# MAIN.net
KiCad netlist of a schematic drawn in Altium Designer
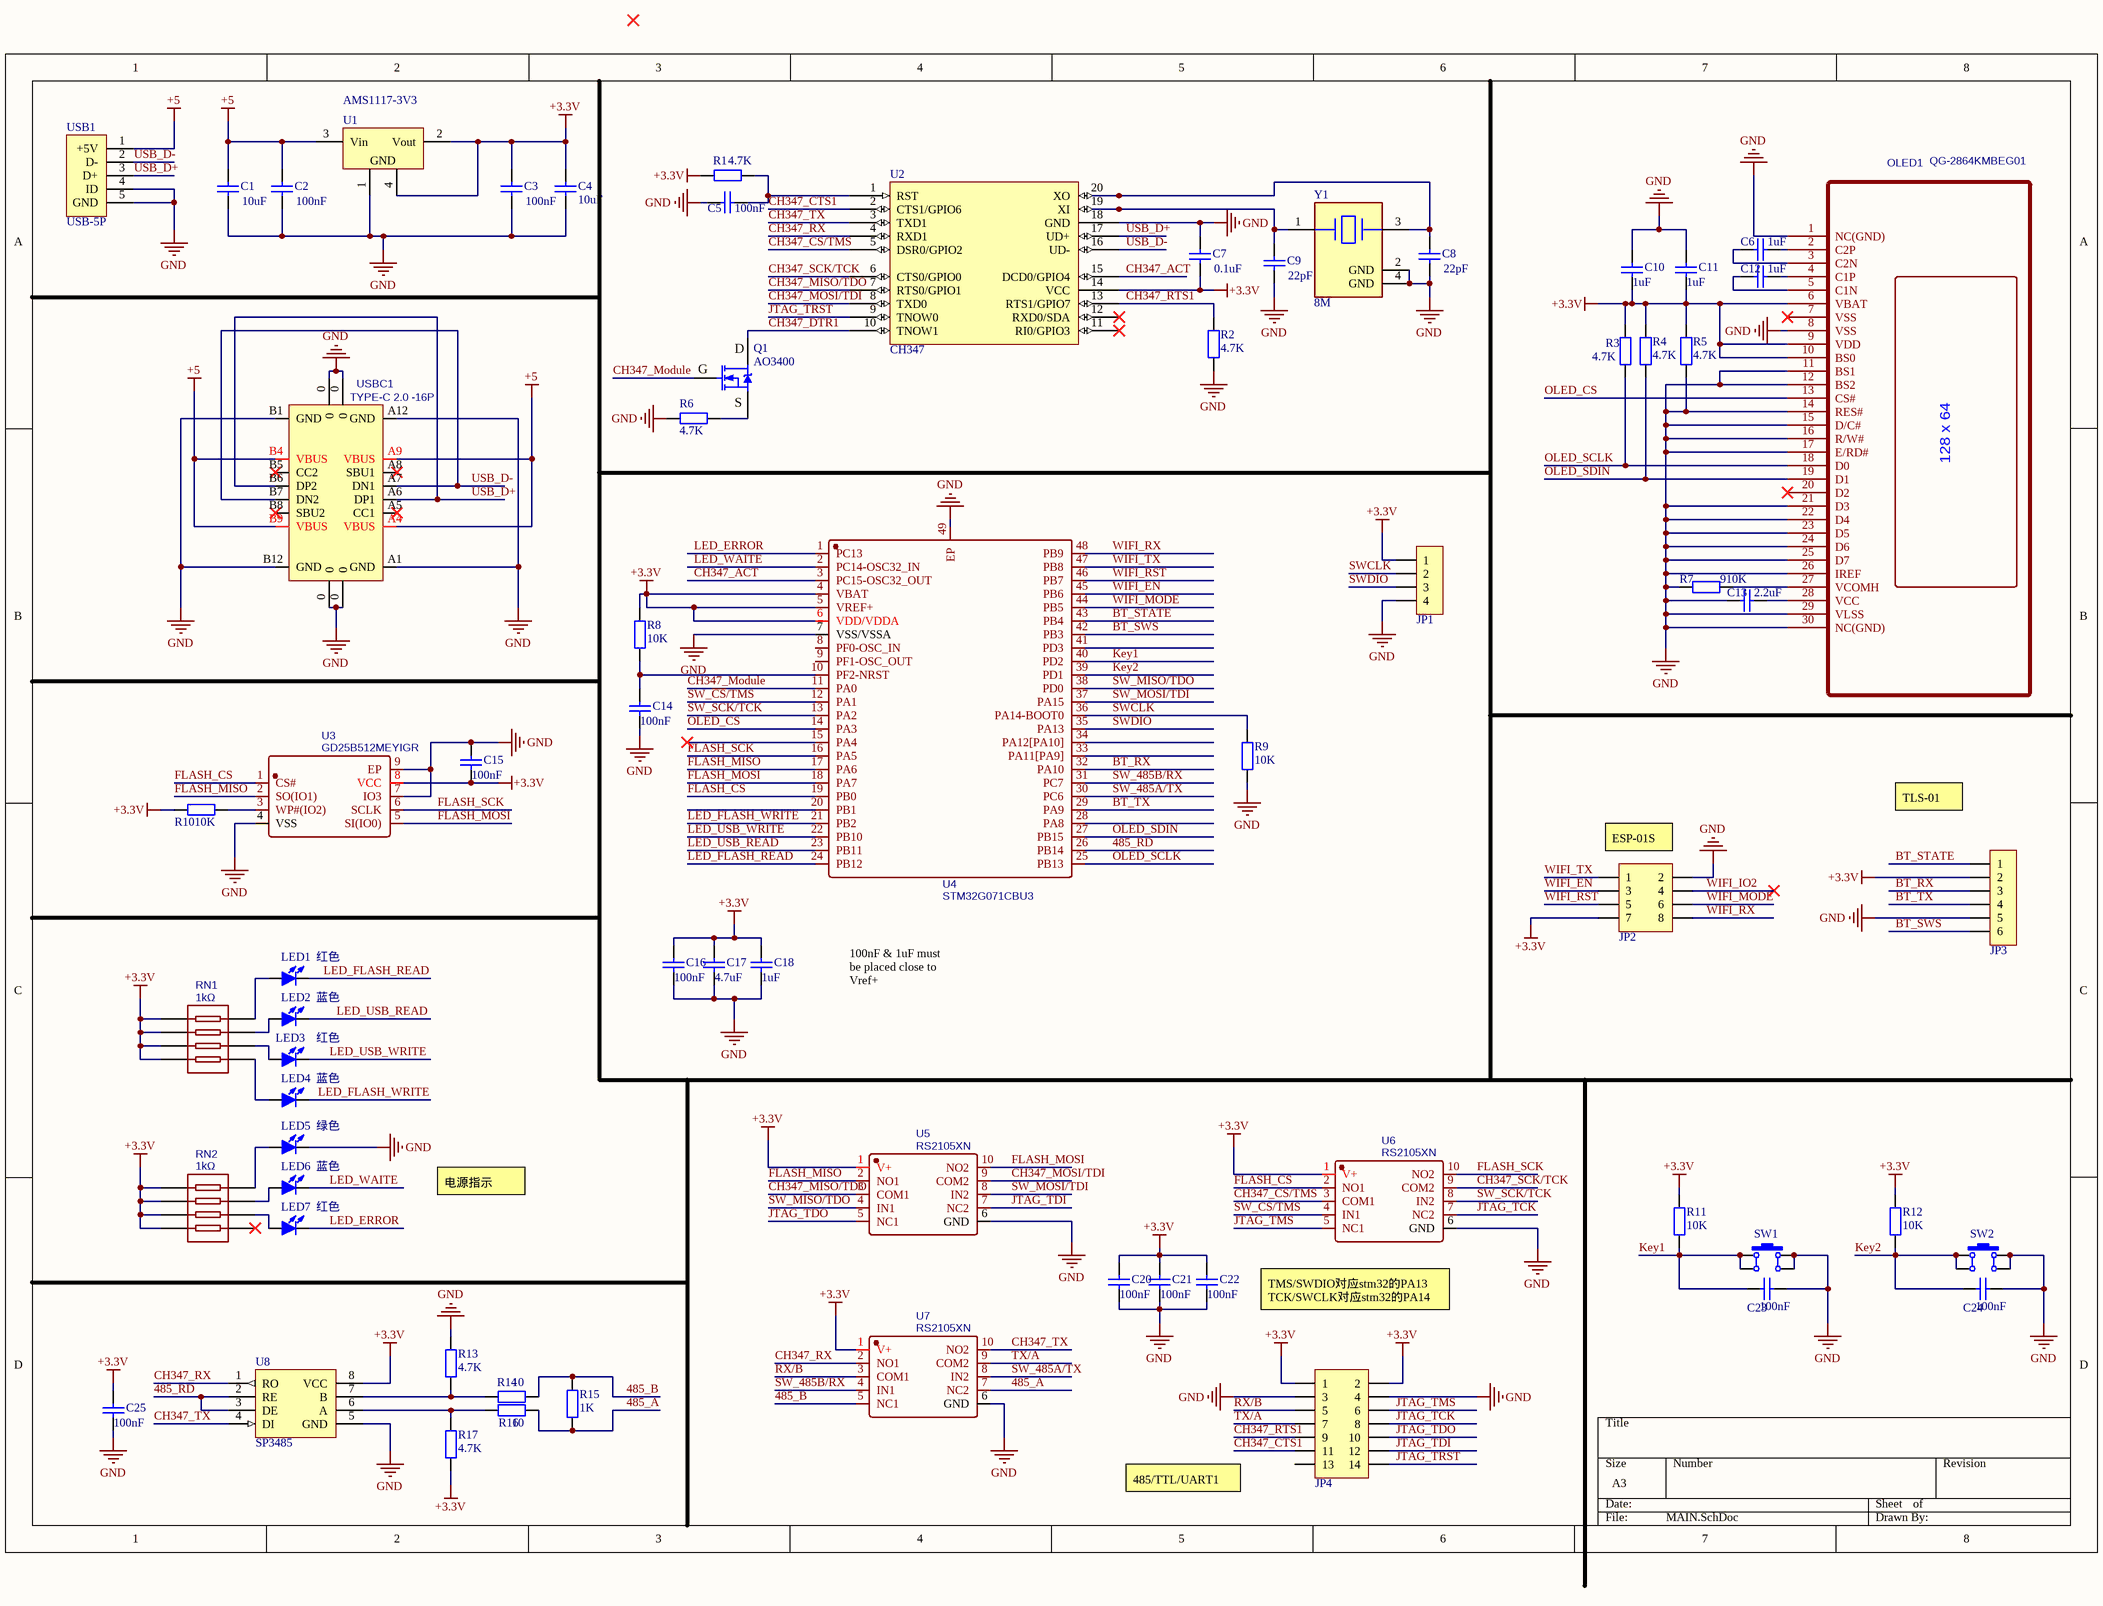
[diagram p0: MAIN.SchDoc]

(export (version "E")
  (design (tool "Eeschema 10.0.6"))
  (components
    (comp (ref "C1")
      (value "10uF")
      (footprint "C0402_M")
      (description "贴片电容")
      (libsource (lib "0.1 - 电阻-电容-电感-电位器") (part "C"))
    )
    (comp (ref "C2")
      (value "100nF")
      (footprint "C0402_M")
      (description "贴片电容")
      (libsource (lib "0.1 - 电阻-电容-电感-电位器") (part "C"))
    )
    (comp (ref "C3")
      (value "100nF")
      (footprint "C0402_M")
      (description "贴片电容")
      (libsource (lib "0.1 - 电阻-电容-电感-电位器") (part "C"))
    )
    (comp (ref "C4")
      (value "10uF")
      (footprint "C0402_M")
      (description "贴片电容")
      (libsource (lib "0.1 - 电阻-电容-电感-电位器") (part "C"))
    )
    (comp (ref "C5")
      (value "100nF")
      (footprint "C0402_M")
      (description "贴片电容")
      (libsource (lib "0.1 - 电阻-电容-电感-电位器") (part "C"))
    )
    (comp (ref "C6")
      (value "1uF")
      (footprint "C0402_M")
      (description "贴片电容")
      (libsource (lib "0.1 - 电阻-电容-电感-电位器") (part "C"))
    )
    (comp (ref "C7")
      (value "0.1uF")
      (footprint "C0402_M")
      (description "贴片电容")
      (libsource (lib "0.1 - 电阻-电容-电感-电位器") (part "C"))
    )
    (comp (ref "C8")
      (value "22pF")
      (footprint "C0402_M")
      (description "贴片电容")
      (libsource (lib "0.1 - 电阻-电容-电感-电位器") (part "C"))
    )
    (comp (ref "C9")
      (value "22pF")
      (footprint "C0402_M")
      (description "贴片电容")
      (libsource (lib "0.1 - 电阻-电容-电感-电位器") (part "C"))
    )
    (comp (ref "C10")
      (value "1uF")
      (footprint "C0402_M")
      (description "贴片电容")
      (libsource (lib "0.1 - 电阻-电容-电感-电位器") (part "C"))
    )
    (comp (ref "C11")
      (value "1uF")
      (footprint "C0402_M")
      (description "贴片电容")
      (libsource (lib "0.1 - 电阻-电容-电感-电位器") (part "C"))
    )
    (comp (ref "C12")
      (value "1uF")
      (footprint "C0402_M")
      (description "贴片电容")
      (libsource (lib "0.1 - 电阻-电容-电感-电位器") (part "C"))
    )
    (comp (ref "C13")
      (value "2.2uF")
      (footprint "C0402_M")
      (description "贴片电容")
      (libsource (lib "0.1 - 电阻-电容-电感-电位器") (part "C"))
    )
    (comp (ref "C14")
      (value "100nF")
      (footprint "C0402_M")
      (description "贴片电容")
      (libsource (lib "0.1 - 电阻-电容-电感-电位器") (part "C"))
    )
    (comp (ref "C15")
      (value "100nF")
      (footprint "C0402_M")
      (description "贴片电容")
      (libsource (lib "0.1 - 电阻-电容-电感-电位器") (part "C"))
    )
    (comp (ref "C16")
      (value "100nF")
      (footprint "C0402_M")
      (description "贴片电容")
      (libsource (lib "0.1 - 电阻-电容-电感-电位器") (part "C"))
    )
    (comp (ref "C17")
      (value "4.7uF")
      (footprint "C0402_M")
      (description "贴片电容")
      (libsource (lib "0.1 - 电阻-电容-电感-电位器") (part "C"))
    )
    (comp (ref "C18")
      (value "1uF")
      (footprint "C0402_M")
      (description "贴片电容")
      (libsource (lib "0.1 - 电阻-电容-电感-电位器") (part "C"))
    )
    (comp (ref "C20")
      (value "100nF")
      (footprint "C0402_M")
      (description "贴片电容")
      (libsource (lib "0.1 - 电阻-电容-电感-电位器") (part "C"))
    )
    (comp (ref "C21")
      (value "100nF")
      (footprint "C0402_M")
      (description "贴片电容")
      (libsource (lib "0.1 - 电阻-电容-电感-电位器") (part "C"))
    )
    (comp (ref "C22")
      (value "100nF")
      (footprint "C0402_M")
      (description "贴片电容")
      (libsource (lib "0.1 - 电阻-电容-电感-电位器") (part "C"))
    )
    (comp (ref "C23")
      (value "100nF")
      (footprint "C0402_M")
      (description "贴片电容")
      (libsource (lib "0.1 - 电阻-电容-电感-电位器") (part "C"))
    )
    (comp (ref "C24")
      (value "100nF")
      (footprint "C0402_M")
      (description "贴片电容")
      (libsource (lib "0.1 - 电阻-电容-电感-电位器") (part "C"))
    )
    (comp (ref "C25")
      (value "100nF")
      (footprint "C0402_M")
      (description "贴片电容")
      (libsource (lib "0.1 - 电阻-电容-电感-电位器") (part "C"))
    )
    (comp (ref "JP1")
      (value "HDR-1X4")
      (footprint "HDR2.54-LI-4P")
      (description "4P接插件")
      (libsource (lib "5.4 - 接插件-脚距2.54 (100mil) ") (part "Header 4"))
    )
    (comp (ref "JP2")
      (value "Header 4X2")
      (footprint "HDR2.54-LI-2x4P")
      (description "4*2P接插件")
      (libsource (lib "5.4 - 接插件-脚距2.54 (100mil) ") (part "Header 4X2"))
    )
    (comp (ref "JP3")
      (value "HDR-1X6")
      (footprint "HDR2.54-LI-6P")
      (description "6P接插件")
      (libsource (lib "5.4 - 接插件-脚距2.54 (100mil) ") (part "Header 6"))
    )
    (comp (ref "JP4")
      (value "Header 2X7")
      (footprint "HDR2.54-WI-2x7P")
      (description "7*2P接插件")
      (libsource (lib "5.4 - 接插件-脚距2.54 (100mil) ") (part "Header 7X2"))
    )
    (comp (ref "LED1")
      (value "红色")
      (footprint "LED0603_R")
      (description "贴片LED")
      (libsource (lib "0.3 - LED发光二极管") (part "LED-SMD"))
    )
    (comp (ref "LED2")
      (value "蓝色")
      (footprint "LED0603_R")
      (description "贴片LED")
      (libsource (lib "0.3 - LED发光二极管") (part "LED-SMD"))
    )
    (comp (ref "LED3")
      (value "红色")
      (footprint "LED0603_R")
      (description "贴片LED")
      (libsource (lib "0.3 - LED发光二极管") (part "LED-SMD"))
    )
    (comp (ref "LED4")
      (value "蓝色")
      (footprint "LED0603_R")
      (description "贴片LED")
      (libsource (lib "0.3 - LED发光二极管") (part "LED-SMD"))
    )
    (comp (ref "LED5")
      (value "绿色")
      (footprint "LED0603_R")
      (description "贴片LED")
      (libsource (lib "0.3 - LED发光二极管") (part "LED-SMD"))
    )
    (comp (ref "LED6")
      (value "蓝色")
      (footprint "LED0603_R")
      (description "贴片LED")
      (libsource (lib "0.3 - LED发光二极管") (part "LED-SMD"))
    )
    (comp (ref "LED7")
      (value "红色")
      (footprint "LED0603_R")
      (description "贴片LED")
      (libsource (lib "0.3 - LED发光二极管") (part "LED-SMD"))
    )
    (comp (ref "OLED1")
      (value "QG-2864KMBEG01")
      (footprint "OLED-SMD_QG-2864XXX")
      (fields (field (name "BOM_SUPPLIER PART") "C91756"))
      (libsource (lib "altium-import") (part "root_3_QG-2864KMBEG01_"))
    )
    (comp (ref "Q1")
      (value "AO3400")
      (footprint "SOT23-3L")
      (description "N沟道 30V/4.2A")
      (libsource (lib "0.4 - 三极管-场效应管-可控硅") (part "AO3400"))
    )
    (comp (ref "R1")
      (value "4.7K")
      (footprint "R0402_M")
      (description "贴片电阻")
      (libsource (lib "0.1 - 电阻-电容-电感-电位器") (part "R"))
    )
    (comp (ref "R2")
      (value "4.7K")
      (footprint "R0402_M")
      (description "贴片电阻")
      (libsource (lib "0.1 - 电阻-电容-电感-电位器") (part "R"))
    )
    (comp (ref "R3")
      (value "4.7K")
      (footprint "R0402_M")
      (description "贴片电阻")
      (libsource (lib "0.1 - 电阻-电容-电感-电位器") (part "R"))
    )
    (comp (ref "R4")
      (value "4.7K")
      (footprint "R0402_M")
      (description "贴片电阻")
      (libsource (lib "0.1 - 电阻-电容-电感-电位器") (part "R"))
    )
    (comp (ref "R5")
      (value "4.7K")
      (footprint "R0402_M")
      (description "贴片电阻")
      (libsource (lib "0.1 - 电阻-电容-电感-电位器") (part "R"))
    )
    (comp (ref "R6")
      (value "4.7K")
      (footprint "R0402_M")
      (description "贴片电阻")
      (libsource (lib "0.1 - 电阻-电容-电感-电位器") (part "R"))
    )
    (comp (ref "R7")
      (value "910K")
      (footprint "R0402_M")
      (description "贴片电阻")
      (libsource (lib "0.1 - 电阻-电容-电感-电位器") (part "R"))
    )
    (comp (ref "R8")
      (value "10K")
      (footprint "R0402_M")
      (description "贴片电阻")
      (libsource (lib "0.1 - 电阻-电容-电感-电位器") (part "R"))
    )
    (comp (ref "R9")
      (value "10K")
      (footprint "R0402_M")
      (description "贴片电阻")
      (libsource (lib "0.1 - 电阻-电容-电感-电位器") (part "R"))
    )
    (comp (ref "R10")
      (value "10K")
      (footprint "R0402_M")
      (description "贴片电阻")
      (libsource (lib "0.1 - 电阻-电容-电感-电位器") (part "R"))
    )
    (comp (ref "R11")
      (value "10K")
      (footprint "R0402_M")
      (description "贴片电阻")
      (libsource (lib "0.1 - 电阻-电容-电感-电位器") (part "R"))
    )
    (comp (ref "R12")
      (value "10K")
      (footprint "R0402_M")
      (description "贴片电阻")
      (libsource (lib "0.1 - 电阻-电容-电感-电位器") (part "R"))
    )
    (comp (ref "R13")
      (value "4.7K")
      (footprint "R0402_M")
      (description "贴片电阻")
      (libsource (lib "0.1 - 电阻-电容-电感-电位器") (part "R"))
    )
    (comp (ref "R14")
      (value "10")
      (footprint "R0402_M")
      (description "贴片电阻")
      (libsource (lib "0.1 - 电阻-电容-电感-电位器") (part "R"))
    )
    (comp (ref "R15")
      (value "1K")
      (footprint "R0402_M")
      (description "贴片电阻")
      (libsource (lib "0.1 - 电阻-电容-电感-电位器") (part "R"))
    )
    (comp (ref "R16")
      (value "10")
      (footprint "R0402_M")
      (description "贴片电阻")
      (libsource (lib "0.1 - 电阻-电容-电感-电位器") (part "R"))
    )
    (comp (ref "R17")
      (value "4.7K")
      (footprint "R0402_M")
      (description "贴片电阻")
      (libsource (lib "0.1 - 电阻-电容-电感-电位器") (part "R"))
    )
    (comp (ref "RN1")
      (value "1kΩ")
      (footprint "RES-ARRAY-SMD_0402-8P-L2.0-W1.0-BL")
      (fields
        (field (name "BOM_MANUFACTURER PART") "4D02WGJ0102TCE")
        (field (name "BOM_SUPPLIER PART") "C25726")
      )
      (libsource (lib "altium-import") (part "root_0_1kΩ_"))
    )
    (comp (ref "RN2")
      (value "1kΩ")
      (footprint "RES-ARRAY-SMD_0402-8P-L2.0-W1.0-BL")
      (fields
        (field (name "BOM_MANUFACTURER PART") "4D02WGJ0102TCE")
        (field (name "BOM_SUPPLIER PART") "C25726")
      )
      (libsource (lib "altium-import") (part "root_0_1kΩ_"))
    )
    (comp (ref "SW1")
      (value "6x6x5")
      (footprint "SW SMD-6*6*6")
      (description "贴片6x6轻触开关")
      (libsource (lib "0.7 - 常用按键-开关-蜂鸣器-电池-测试点") (part "TSW SMD-6x6"))
    )
    (comp (ref "SW2")
      (value "6x6x5")
      (footprint "SW SMD-6*6*6")
      (description "贴片6x6轻触开关")
      (libsource (lib "0.7 - 常用按键-开关-蜂鸣器-电池-测试点") (part "TSW SMD-6x6"))
    )
    (comp (ref "U1")
      (value "AMS1117-3V3")
      (footprint "SOT223_L")
      (description "三端稳压芯片")
      (libsource (lib "1.1 - 电源类芯片") (part "AMS1117"))
    )
    (comp (ref "U2") (value "CH347") (footprint "TSSOP-20") (libsource (lib "沁恒") (part "CH347")))
    (comp (ref "U3")
      (value "GD25B512MEYIGR")
      (footprint "WSON-8_L8.0-W6.0-P1.27-TL-EP-1")
      (fields (field (name "BOM_SUPPLIER PART") "C2974186") (field (name "CONTRIBUTOR") "LCSC"))
      (libsource (lib "altium-import") (part "root_0_GD25B512MEYIGR_"))
    )
    (comp (ref "U4")
      (value "STM32G071CBU3")
      (footprint "VFQFPN48_M")
      (fields (field (name "BOM_SUPPLIER PART") "C724076") (field (name "CONTRIBUTOR") "LCSC"))
      (libsource (lib "altium-import") (part "root_0_STM32G071CBU3_"))
    )
    (comp (ref "U5")
      (value "RS2105XN")
      (footprint "MSOP10_L")
      (fields (field (name "BOM_SUPPLIER PART") "C237025") (field (name "CONTRIBUTOR") "LCSC"))
      (libsource (lib "altium-import") (part "root_0_RS2105XN_"))
    )
    (comp (ref "U6")
      (value "RS2105XN")
      (footprint "MSOP10_L")
      (fields (field (name "BOM_SUPPLIER PART") "C237025") (field (name "CONTRIBUTOR") "LCSC"))
      (libsource (lib "altium-import") (part "root_0_RS2105XN_"))
    )
    (comp (ref "U7")
      (value "RS2105XN")
      (footprint "MSOP10_L")
      (fields (field (name "BOM_SUPPLIER PART") "C237025") (field (name "CONTRIBUTOR") "LCSC"))
      (libsource (lib "altium-import") (part "root_0_RS2105XN_"))
    )
    (comp (ref "U8")
      (value "SP3485")
      (footprint "SOP8_N")
      (description "RS485总线收发芯片")
      (libsource (lib "1.0 - 常见芯片") (part "SP3485"))
    )
    (comp (ref "USB1")
      (value "USB-5P")
      (footprint "USB-MICRO_E")
      (description "微型USB母座")
      (libsource (lib "0.8 - 以太网-音频-Type-C USB插座") (part "USB-5P"))
    )
    (comp (ref "USBC1")
      (value "TYPE-C 2.0 -16P")
      (footprint "USB-C-SMD_16P")
      (description "USB2.0 Type-C 16Pin  母座")
      (libsource (lib "0.8 - 以太网-音频-Type-C USB插座") (part "USB2.0_Type-C_16Pin"))
    )
    (comp (ref "Y1")
      (value "8M")
      (footprint "FP-ABM11W-MFG")
      (description "CRYSTAL 32.0000MHZ 8PF SMD")
      (libsource (lib "Altium Content Vault") (part "5fba445d8d5f95165d6b3865099b029"))
    )
  )
  (nets
    (net (code "1") (name "+3.3V") (class "Default")
      (node (ref "C10") (pin "2") (pinfunction "2_2") (pintype "passive"))
      (node (ref "C11") (pin "2") (pinfunction "2_2") (pintype "passive"))
      (node (ref "C15") (pin "2") (pinfunction "2_2") (pintype "passive"))
      (node (ref "C16") (pin "1") (pinfunction "1_1") (pintype "passive"))
      (node (ref "C17") (pin "1") (pinfunction "1_1") (pintype "passive"))
      (node (ref "C18") (pin "1") (pinfunction "1_1") (pintype "passive"))
      (node (ref "C20") (pin "1") (pinfunction "1_1") (pintype "passive"))
      (node (ref "C21") (pin "1") (pinfunction "1_1") (pintype "passive"))
      (node (ref "C22") (pin "1") (pinfunction "1_1") (pintype "passive"))
      (node (ref "C25") (pin "1") (pinfunction "1_1") (pintype "passive"))
      (node (ref "C3") (pin "2") (pinfunction "2_2") (pintype "passive"))
      (node (ref "C4") (pin "2") (pinfunction "2_2") (pintype "passive"))
      (node (ref "C7") (pin "1") (pinfunction "1_1") (pintype "passive"))
      (node (ref "JP1") (pin "1") (pinfunction "1_1") (pintype "passive"))
      (node (ref "JP2") (pin "7") (pinfunction "7_7") (pintype "passive"))
      (node (ref "JP3") (pin "2") (pinfunction "2_2") (pintype "passive"))
      (node (ref "JP4") (pin "1") (pinfunction "1_1") (pintype "passive"))
      (node (ref "JP4") (pin "2") (pinfunction "2_2") (pintype "passive"))
      (node (ref "OLED1") (pin "10") (pinfunction "BS0_10") (pintype "passive"))
      (node (ref "OLED1") (pin "6") (pinfunction "VBAT_6") (pintype "passive"))
      (node (ref "OLED1") (pin "9") (pinfunction "VDD_9") (pintype "passive"))
      (node (ref "R1") (pin "1") (pinfunction "1_1") (pintype "passive"))
      (node (ref "R10") (pin "2") (pinfunction "2_2") (pintype "passive"))
      (node (ref "R11") (pin "2") (pinfunction "2_2") (pintype "passive"))
      (node (ref "R12") (pin "2") (pinfunction "2_2") (pintype "passive"))
      (node (ref "R17") (pin "1") (pinfunction "1_1") (pintype "passive"))
      (node (ref "R3") (pin "1") (pinfunction "1_1") (pintype "passive"))
      (node (ref "R4") (pin "1") (pinfunction "1_1") (pintype "passive"))
      (node (ref "R5") (pin "1") (pinfunction "1_1") (pintype "passive"))
      (node (ref "R8") (pin "2") (pinfunction "2_2") (pintype "passive"))
      (node (ref "RN1") (pin "1") (pinfunction "1_1") (pintype "passive"))
      (node (ref "RN1") (pin "2") (pinfunction "2_2") (pintype "passive"))
      (node (ref "RN1") (pin "3") (pinfunction "3_3") (pintype "passive"))
      (node (ref "RN1") (pin "4") (pinfunction "4_4") (pintype "passive"))
      (node (ref "RN2") (pin "1") (pinfunction "1_1") (pintype "passive"))
      (node (ref "RN2") (pin "2") (pinfunction "2_2") (pintype "passive"))
      (node (ref "RN2") (pin "3") (pinfunction "3_3") (pintype "passive"))
      (node (ref "RN2") (pin "4") (pinfunction "4_4") (pintype "passive"))
      (node (ref "U1") (pin "2") (pinfunction "Vout_2") (pintype "passive"))
      (node (ref "U1") (pin "4") (pinfunction "GND_4") (pintype "passive"))
      (node (ref "U2") (pin "14") (pinfunction "VCC_14") (pintype "power_in"))
      (node (ref "U3") (pin "8") (pinfunction "VCC_8") (pintype "passive"))
      (node (ref "U4") (pin "4") (pinfunction "VBAT_4") (pintype "passive"))
      (node (ref "U4") (pin "5") (pinfunction "VREF+_5") (pintype "passive"))
      (node (ref "U4") (pin "6") (pinfunction "VDD/VDDA_6") (pintype "passive"))
      (node (ref "U5") (pin "1") (pinfunction "V+_1") (pintype "passive"))
      (node (ref "U6") (pin "1") (pinfunction "V+_1") (pintype "passive"))
      (node (ref "U7") (pin "1") (pinfunction "V+_1") (pintype "passive"))
      (node (ref "U8") (pin "8") (pinfunction "VCC_8") (pintype "passive"))
    )
    (net (code "2") (name "+5") (class "Default")
      (node (ref "C1") (pin "2") (pinfunction "2_2") (pintype "passive"))
      (node (ref "C2") (pin "2") (pinfunction "2_2") (pintype "passive"))
      (node (ref "U1") (pin "3") (pinfunction "Vin_3") (pintype "passive"))
      (node (ref "USB1") (pin "1") (pinfunction "+5V_1") (pintype "passive"))
      (node (ref "USBC1") (pin "A4") (pinfunction "VBUS_A4") (pintype "passive"))
      (node (ref "USBC1") (pin "A9") (pinfunction "VBUS_A9") (pintype "passive"))
      (node (ref "USBC1") (pin "B4") (pinfunction "VBUS_B4") (pintype "passive"))
      (node (ref "USBC1") (pin "B9") (pinfunction "VBUS_B9") (pintype "passive"))
    )
    (net (code "3") (name "/485_A") (class "Default")
      (node (ref "R15") (pin "1") (pinfunction "1_1") (pintype "passive"))
      (node (ref "R16") (pin "1") (pinfunction "1_1") (pintype "passive"))
      (node (ref "U7") (pin "7") (pinfunction "NC2_7") (pintype "passive"))
    )
    (net (code "4") (name "/485_B") (class "Default")
      (node (ref "R14") (pin "1") (pinfunction "1_1") (pintype "passive"))
      (node (ref "R15") (pin "2") (pinfunction "2_2") (pintype "passive"))
      (node (ref "U7") (pin "5") (pinfunction "NC1_5") (pintype "passive"))
    )
    (net (code "5") (name "/485_RD") (class "Default")
      (node (ref "U4") (pin "26") (pinfunction "PB14_26") (pintype "passive"))
      (node (ref "U8") (pin "2") (pinfunction "RE_2") (pintype "passive"))
      (node (ref "U8") (pin "3") (pinfunction "DE_3") (pintype "passive"))
    )
    (net (code "6") (name "/BT_RX") (class "Default")
      (node (ref "JP3") (pin "3") (pinfunction "3_3") (pintype "passive"))
      (node (ref "U4") (pin "32") (pinfunction "PA10_32") (pintype "passive"))
    )
    (net (code "7") (name "/BT_STATE") (class "Default")
      (node (ref "JP3") (pin "1") (pinfunction "1_1") (pintype "passive"))
      (node (ref "U4") (pin "43") (pinfunction "PB4_43") (pintype "passive"))
    )
    (net (code "8") (name "/BT_SWS") (class "Default")
      (node (ref "JP3") (pin "6") (pinfunction "6_6") (pintype "passive"))
      (node (ref "U4") (pin "42") (pinfunction "PB3_42") (pintype "passive"))
    )
    (net (code "9") (name "/BT_TX") (class "Default")
      (node (ref "JP3") (pin "4") (pinfunction "4_4") (pintype "passive"))
      (node (ref "U4") (pin "29") (pinfunction "PA9_29") (pintype "passive"))
    )
    (net (code "10") (name "/CH347_ACT") (class "Default")
      (node (ref "U2") (pin "15") (pinfunction "DCD0/GPIO4_15") (pintype "bidirectional"))
      (node (ref "U4") (pin "3") (pinfunction "PC15-OSC32_OUT_3") (pintype "passive"))
    )
    (net (code "11") (name "/CH347_CTS1") (class "Default")
      (node (ref "JP4") (pin "11") (pinfunction "11_11") (pintype "passive"))
      (node (ref "U2") (pin "2") (pinfunction "CTS1/GPIO6_2") (pintype "bidirectional"))
    )
    (net (code "12") (name "/CH347_DTR1") (class "Default")
      (node (ref "Q1") (pin "3") (pinfunction "D_3") (pintype "passive"))
      (node (ref "U2") (pin "10") (pinfunction "TNOW1_10") (pintype "bidirectional"))
    )
    (net (code "13") (name "/CH347_MISO{slash}TDO") (class "Default")
      (node (ref "U2") (pin "7") (pinfunction "RTS0/GPIO1_7") (pintype "bidirectional"))
      (node (ref "U5") (pin "3") (pinfunction "COM1_3") (pintype "passive"))
    )
    (net (code "14") (name "/CH347_MOSI{slash}TDI") (class "Default")
      (node (ref "U2") (pin "8") (pinfunction "TXD0_8") (pintype "bidirectional"))
      (node (ref "U5") (pin "9") (pinfunction "COM2_9") (pintype "passive"))
    )
    (net (code "15") (name "/CH347_Module") (class "Default")
      (node (ref "Q1") (pin "1") (pinfunction "G_1") (pintype "passive"))
      (node (ref "U4") (pin "11") (pinfunction "PA0_11") (pintype "passive"))
    )
    (net (code "16") (name "/CH347_RTS1") (class "Default")
      (node (ref "JP4") (pin "9") (pinfunction "9_9") (pintype "passive"))
      (node (ref "R2") (pin "2") (pinfunction "2_2") (pintype "passive"))
      (node (ref "U2") (pin "13") (pinfunction "RTS1/GPIO7_13") (pintype "bidirectional"))
    )
    (net (code "17") (name "/CH347_RX") (class "Default")
      (node (ref "U2") (pin "4") (pinfunction "RXD1_4") (pintype "bidirectional"))
      (node (ref "U7") (pin "2") (pinfunction "NO1_2") (pintype "passive"))
      (node (ref "U8") (pin "1") (pinfunction "RO_1") (pintype "output"))
    )
    (net (code "18") (name "/CH347_SCK{slash}TCK") (class "Default")
      (node (ref "U2") (pin "6") (pinfunction "CTS0/GPIO0_6") (pintype "bidirectional"))
      (node (ref "U6") (pin "9") (pinfunction "COM2_9") (pintype "passive"))
    )
    (net (code "19") (name "/CH347_TX") (class "Default")
      (node (ref "U2") (pin "3") (pinfunction "TXD1_3") (pintype "bidirectional"))
      (node (ref "U7") (pin "10") (pinfunction "NO2_10") (pintype "passive"))
      (node (ref "U8") (pin "4") (pinfunction "DI_4") (pintype "input"))
    )
    (net (code "20") (name "/CH347_~{CS}{slash}TMS") (class "Default")
      (node (ref "U2") (pin "5") (pinfunction "DSR0/GPIO2_5") (pintype "bidirectional"))
      (node (ref "U6") (pin "3") (pinfunction "COM1_3") (pintype "passive"))
    )
    (net (code "21") (name "/FLASH_CS") (class "Default")
      (node (ref "U3") (pin "1") (pinfunction "CS#_1") (pintype "passive"))
      (node (ref "U4") (pin "19") (pinfunction "PB0_19") (pintype "passive"))
      (node (ref "U6") (pin "2") (pinfunction "NO1_2") (pintype "passive"))
    )
    (net (code "22") (name "/FLASH_MISO") (class "Default")
      (node (ref "U3") (pin "2") (pinfunction "SO(IO1)_2") (pintype "passive"))
      (node (ref "U4") (pin "17") (pinfunction "PA6_17") (pintype "passive"))
      (node (ref "U5") (pin "2") (pinfunction "NO1_2") (pintype "passive"))
    )
    (net (code "23") (name "/FLASH_MOSI") (class "Default")
      (node (ref "U3") (pin "5") (pinfunction "SI(IO0)_5") (pintype "passive"))
      (node (ref "U4") (pin "18") (pinfunction "PA7_18") (pintype "passive"))
      (node (ref "U5") (pin "10") (pinfunction "NO2_10") (pintype "passive"))
    )
    (net (code "24") (name "/FLASH_SCK") (class "Default")
      (node (ref "U3") (pin "6") (pinfunction "SCLK_6") (pintype "passive"))
      (node (ref "U4") (pin "16") (pinfunction "PA5_16") (pintype "passive"))
      (node (ref "U6") (pin "10") (pinfunction "NO2_10") (pintype "passive"))
    )
    (net (code "25") (name "/JTAG_TCK") (class "Default")
      (node (ref "JP4") (pin "8") (pinfunction "8_8") (pintype "passive"))
      (node (ref "U6") (pin "7") (pinfunction "NC2_7") (pintype "passive"))
    )
    (net (code "26") (name "/JTAG_TDI") (class "Default")
      (node (ref "JP4") (pin "12") (pinfunction "12_12") (pintype "passive"))
      (node (ref "U5") (pin "7") (pinfunction "NC2_7") (pintype "passive"))
    )
    (net (code "27") (name "/JTAG_TDO") (class "Default")
      (node (ref "JP4") (pin "10") (pinfunction "10_10") (pintype "passive"))
      (node (ref "U5") (pin "5") (pinfunction "NC1_5") (pintype "passive"))
    )
    (net (code "28") (name "/JTAG_TMS") (class "Default")
      (node (ref "JP4") (pin "6") (pinfunction "6_6") (pintype "passive"))
      (node (ref "U6") (pin "5") (pinfunction "NC1_5") (pintype "passive"))
    )
    (net (code "29") (name "/JTAG_TRST") (class "Default")
      (node (ref "JP4") (pin "14") (pinfunction "14_14") (pintype "passive"))
      (node (ref "U2") (pin "9") (pinfunction "TNOW0_9") (pintype "bidirectional"))
    )
    (net (code "30") (name "/Key1") (class "Default")
      (node (ref "C23") (pin "1") (pinfunction "1_1") (pintype "passive"))
      (node (ref "R11") (pin "1") (pinfunction "1_1") (pintype "passive"))
      (node (ref "SW1") (pin "1") (pinfunction "1_1") (pintype "passive"))
      (node (ref "SW1") (pin "4") (pinfunction "4_4") (pintype "passive"))
      (node (ref "U4") (pin "40") (pinfunction "PD2_40") (pintype "passive"))
    )
    (net (code "31") (name "/Key2") (class "Default")
      (node (ref "C24") (pin "1") (pinfunction "1_1") (pintype "passive"))
      (node (ref "R12") (pin "1") (pinfunction "1_1") (pintype "passive"))
      (node (ref "SW2") (pin "1") (pinfunction "1_1") (pintype "passive"))
      (node (ref "SW2") (pin "4") (pinfunction "4_4") (pintype "passive"))
      (node (ref "U4") (pin "39") (pinfunction "PD1_39") (pintype "passive"))
    )
    (net (code "32") (name "/LED_ERROR") (class "Default")
      (node (ref "LED7") (pin "2") (pinfunction "K_2") (pintype "passive"))
      (node (ref "U4") (pin "1") (pinfunction "PC13_1") (pintype "passive"))
    )
    (net (code "33") (name "/LED_FLASH_READ") (class "Default")
      (node (ref "LED1") (pin "2") (pinfunction "K_2") (pintype "passive"))
      (node (ref "U4") (pin "24") (pinfunction "PB12_24") (pintype "passive"))
    )
    (net (code "34") (name "/LED_FLASH_WRITE") (class "Default")
      (node (ref "LED4") (pin "2") (pinfunction "K_2") (pintype "passive"))
      (node (ref "U4") (pin "21") (pinfunction "PB2_21") (pintype "passive"))
    )
    (net (code "35") (name "/LED_USB_READ") (class "Default")
      (node (ref "LED2") (pin "2") (pinfunction "K_2") (pintype "passive"))
      (node (ref "U4") (pin "23") (pinfunction "PB11_23") (pintype "passive"))
    )
    (net (code "36") (name "/LED_USB_WRITE") (class "Default")
      (node (ref "LED3") (pin "2") (pinfunction "K_2") (pintype "passive"))
      (node (ref "U4") (pin "22") (pinfunction "PB10_22") (pintype "passive"))
    )
    (net (code "37") (name "/LED_WAITE") (class "Default")
      (node (ref "LED6") (pin "2") (pinfunction "K_2") (pintype "passive"))
      (node (ref "U4") (pin "2") (pinfunction "PC14-OSC32_IN_2") (pintype "passive"))
    )
    (net (code "38") (name "/OLED_CS") (class "Default")
      (node (ref "OLED1") (pin "13") (pinfunction "CS#_13") (pintype "passive"))
      (node (ref "U4") (pin "14") (pinfunction "PA3_14") (pintype "passive"))
    )
    (net (code "39") (name "/OLED_SCLK") (class "Default")
      (node (ref "OLED1") (pin "18") (pinfunction "D0_18") (pintype "passive"))
      (node (ref "R3") (pin "2") (pinfunction "2_2") (pintype "passive"))
      (node (ref "U4") (pin "25") (pinfunction "PB13_25") (pintype "passive"))
    )
    (net (code "40") (name "/OLED_SDIN") (class "Default")
      (node (ref "OLED1") (pin "19") (pinfunction "D1_19") (pintype "passive"))
      (node (ref "R4") (pin "2") (pinfunction "2_2") (pintype "passive"))
      (node (ref "U4") (pin "27") (pinfunction "PB15_27") (pintype "passive"))
    )
    (net (code "41") (name "/RX{slash}B") (class "Default")
      (node (ref "JP4") (pin "5") (pinfunction "5_5") (pintype "passive"))
      (node (ref "U7") (pin "3") (pinfunction "COM1_3") (pintype "passive"))
    )
    (net (code "42") (name "/SWCLK") (class "Default")
      (node (ref "JP1") (pin "2") (pinfunction "2_2") (pintype "passive"))
      (node (ref "R9") (pin "1") (pinfunction "1_1") (pintype "passive"))
      (node (ref "U4") (pin "36") (pinfunction "PA14-BOOT0_36") (pintype "passive"))
    )
    (net (code "43") (name "/SWDIO") (class "Default")
      (node (ref "JP1") (pin "3") (pinfunction "3_3") (pintype "passive"))
      (node (ref "U4") (pin "35") (pinfunction "PA13_35") (pintype "passive"))
    )
    (net (code "44") (name "/SW_485A{slash}TX") (class "Default")
      (node (ref "U4") (pin "30") (pinfunction "PC6_30") (pintype "passive"))
      (node (ref "U7") (pin "8") (pinfunction "IN2_8") (pintype "passive"))
    )
    (net (code "45") (name "/SW_485B{slash}RX") (class "Default")
      (node (ref "U4") (pin "31") (pinfunction "PC7_31") (pintype "passive"))
      (node (ref "U7") (pin "4") (pinfunction "IN1_4") (pintype "passive"))
    )
    (net (code "46") (name "/SW_MISO{slash}TDO") (class "Default")
      (node (ref "U4") (pin "38") (pinfunction "PD0_38") (pintype "passive"))
      (node (ref "U5") (pin "4") (pinfunction "IN1_4") (pintype "passive"))
    )
    (net (code "47") (name "/SW_MOSI{slash}TDI") (class "Default")
      (node (ref "U4") (pin "37") (pinfunction "PA15_37") (pintype "passive"))
      (node (ref "U5") (pin "8") (pinfunction "IN2_8") (pintype "passive"))
    )
    (net (code "48") (name "/SW_SCK{slash}TCK") (class "Default")
      (node (ref "U4") (pin "13") (pinfunction "PA2_13") (pintype "passive"))
      (node (ref "U6") (pin "8") (pinfunction "IN2_8") (pintype "passive"))
    )
    (net (code "49") (name "/SW_~{CS}{slash}TMS") (class "Default")
      (node (ref "U4") (pin "12") (pinfunction "PA1_12") (pintype "passive"))
      (node (ref "U6") (pin "4") (pinfunction "IN1_4") (pintype "passive"))
    )
    (net (code "50") (name "/TX{slash}A") (class "Default")
      (node (ref "JP4") (pin "7") (pinfunction "7_7") (pintype "passive"))
      (node (ref "U7") (pin "9") (pinfunction "COM2_9") (pintype "passive"))
    )
    (net (code "51") (name "/USB_D+") (class "Default")
      (node (ref "U2") (pin "17") (pinfunction "UD+_17") (pintype "bidirectional"))
      (node (ref "USB1") (pin "3") (pinfunction "D+_3") (pintype "passive"))
      (node (ref "USBC1") (pin "A6") (pinfunction "DP1_A6") (pintype "passive"))
      (node (ref "USBC1") (pin "B6") (pinfunction "DP2_B6") (pintype "passive"))
    )
    (net (code "52") (name "/USB_D-") (class "Default")
      (node (ref "U2") (pin "16") (pinfunction "UD-_16") (pintype "bidirectional"))
      (node (ref "USB1") (pin "2") (pinfunction "D-_2") (pintype "passive"))
      (node (ref "USBC1") (pin "A7") (pinfunction "DN1_A7") (pintype "passive"))
      (node (ref "USBC1") (pin "B7") (pinfunction "DN2_B7") (pintype "passive"))
    )
    (net (code "53") (name "/WIFI_EN") (class "Default")
      (node (ref "JP2") (pin "3") (pinfunction "3_3") (pintype "passive"))
      (node (ref "U4") (pin "45") (pinfunction "PB6_45") (pintype "passive"))
    )
    (net (code "54") (name "/WIFI_IO2") (class "Default")
      (node (ref "JP2") (pin "4") (pinfunction "4_4") (pintype "passive+no_connect"))
    )
    (net (code "55") (name "/WIFI_MODE") (class "Default")
      (node (ref "JP2") (pin "6") (pinfunction "6_6") (pintype "passive"))
      (node (ref "U4") (pin "44") (pinfunction "PB5_44") (pintype "passive"))
    )
    (net (code "56") (name "/WIFI_RST") (class "Default")
      (node (ref "JP2") (pin "5") (pinfunction "5_5") (pintype "passive"))
      (node (ref "U4") (pin "46") (pinfunction "PB7_46") (pintype "passive"))
    )
    (net (code "57") (name "/WIFI_RX") (class "Default")
      (node (ref "JP2") (pin "8") (pinfunction "8_8") (pintype "passive"))
      (node (ref "U4") (pin "48") (pinfunction "PB9_48") (pintype "passive"))
    )
    (net (code "58") (name "/WIFI_TX") (class "Default")
      (node (ref "JP2") (pin "1") (pinfunction "1_1") (pintype "passive"))
      (node (ref "U4") (pin "47") (pinfunction "PB8_47") (pintype "passive"))
    )
    (net (code "59") (name "GND") (class "Default")
      (node (ref "C1") (pin "1") (pinfunction "1_1") (pintype "passive"))
      (node (ref "C10") (pin "1") (pinfunction "1_1") (pintype "passive"))
      (node (ref "C11") (pin "1") (pinfunction "1_1") (pintype "passive"))
      (node (ref "C13") (pin "2") (pinfunction "2_2") (pintype "passive"))
      (node (ref "C14") (pin "2") (pinfunction "2_2") (pintype "passive"))
      (node (ref "C15") (pin "1") (pinfunction "1_1") (pintype "passive"))
      (node (ref "C16") (pin "2") (pinfunction "2_2") (pintype "passive"))
      (node (ref "C17") (pin "2") (pinfunction "2_2") (pintype "passive"))
      (node (ref "C18") (pin "2") (pinfunction "2_2") (pintype "passive"))
      (node (ref "C2") (pin "1") (pinfunction "1_1") (pintype "passive"))
      (node (ref "C20") (pin "2") (pinfunction "2_2") (pintype "passive"))
      (node (ref "C21") (pin "2") (pinfunction "2_2") (pintype "passive"))
      (node (ref "C22") (pin "2") (pinfunction "2_2") (pintype "passive"))
      (node (ref "C23") (pin "2") (pinfunction "2_2") (pintype "passive"))
      (node (ref "C24") (pin "2") (pinfunction "2_2") (pintype "passive"))
      (node (ref "C25") (pin "2") (pinfunction "2_2") (pintype "passive"))
      (node (ref "C3") (pin "1") (pinfunction "1_1") (pintype "passive"))
      (node (ref "C4") (pin "1") (pinfunction "1_1") (pintype "passive"))
      (node (ref "C5") (pin "1") (pinfunction "1_1") (pintype "passive"))
      (node (ref "C7") (pin "2") (pinfunction "2_2") (pintype "passive"))
      (node (ref "C8") (pin "1") (pinfunction "1_1") (pintype "passive"))
      (node (ref "C9") (pin "1") (pinfunction "1_1") (pintype "passive"))
      (node (ref "JP1") (pin "4") (pinfunction "4_4") (pintype "passive"))
      (node (ref "JP2") (pin "2") (pinfunction "2_2") (pintype "passive"))
      (node (ref "JP3") (pin "5") (pinfunction "5_5") (pintype "passive"))
      (node (ref "JP4") (pin "3") (pinfunction "3_3") (pintype "passive"))
      (node (ref "JP4") (pin "4") (pinfunction "4_4") (pintype "passive"))
      (node (ref "LED5") (pin "2") (pinfunction "K_2") (pintype "passive"))
      (node (ref "OLED1") (pin "1") (pinfunction "NC(GND)_1") (pintype "passive"))
      (node (ref "OLED1") (pin "11") (pinfunction "BS1_11") (pintype "passive"))
      (node (ref "OLED1") (pin "12") (pinfunction "BS2_12") (pintype "passive"))
      (node (ref "OLED1") (pin "14") (pinfunction "RES#_14") (pintype "passive"))
      (node (ref "OLED1") (pin "15") (pinfunction "D/C#_15") (pintype "passive"))
      (node (ref "OLED1") (pin "16") (pinfunction "R/W#_16") (pintype "passive"))
      (node (ref "OLED1") (pin "17") (pinfunction "E/RD#_17") (pintype "passive"))
      (node (ref "OLED1") (pin "21") (pinfunction "D3_21") (pintype "passive"))
      (node (ref "OLED1") (pin "22") (pinfunction "D4_22") (pintype "passive"))
      (node (ref "OLED1") (pin "23") (pinfunction "D5_23") (pintype "passive"))
      (node (ref "OLED1") (pin "24") (pinfunction "D6_24") (pintype "passive"))
      (node (ref "OLED1") (pin "25") (pinfunction "D7_25") (pintype "passive"))
      (node (ref "OLED1") (pin "26") (pinfunction "IREF_26") (pintype "passive"))
      (node (ref "OLED1") (pin "29") (pinfunction "VLSS_29") (pintype "passive"))
      (node (ref "OLED1") (pin "30") (pinfunction "NC(GND)_30") (pintype "passive"))
      (node (ref "OLED1") (pin "8") (pinfunction "VSS_8") (pintype "passive"))
      (node (ref "R13") (pin "2") (pinfunction "2_2") (pintype "passive"))
      (node (ref "R2") (pin "1") (pinfunction "1_1") (pintype "passive"))
      (node (ref "R5") (pin "2") (pinfunction "2_2") (pintype "passive"))
      (node (ref "R6") (pin "1") (pinfunction "1_1") (pintype "passive"))
      (node (ref "R7") (pin "1") (pinfunction "1_1") (pintype "passive"))
      (node (ref "R9") (pin "2") (pinfunction "2_2") (pintype "passive"))
      (node (ref "SW1") (pin "2") (pinfunction "2_2") (pintype "passive"))
      (node (ref "SW1") (pin "3") (pinfunction "3_3") (pintype "passive"))
      (node (ref "SW2") (pin "2") (pinfunction "2_2") (pintype "passive"))
      (node (ref "SW2") (pin "3") (pinfunction "3_3") (pintype "passive"))
      (node (ref "U1") (pin "1") (pinfunction "GND_1") (pintype "passive"))
      (node (ref "U2") (pin "18") (pinfunction "GND_18") (pintype "power_in"))
      (node (ref "U3") (pin "4") (pinfunction "VSS_4") (pintype "passive"))
      (node (ref "U3") (pin "7") (pinfunction "IO3_7") (pintype "passive"))
      (node (ref "U3") (pin "9") (pinfunction "EP_9") (pintype "passive"))
      (node (ref "U4") (pin "49") (pinfunction "EP_49") (pintype "passive"))
      (node (ref "U4") (pin "7") (pinfunction "VSS/VSSA_7") (pintype "passive"))
      (node (ref "U5") (pin "6") (pinfunction "GND_6") (pintype "passive"))
      (node (ref "U6") (pin "6") (pinfunction "GND_6") (pintype "passive"))
      (node (ref "U7") (pin "6") (pinfunction "GND_6") (pintype "passive"))
      (node (ref "U8") (pin "5") (pinfunction "GND_5") (pintype "passive"))
      (node (ref "USB1") (pin "4") (pinfunction "ID_4") (pintype "passive"))
      (node (ref "USB1") (pin "5") (pinfunction "GND_5") (pintype "passive"))
      (node (ref "USBC1") (pin "0") (pinfunction "0_0") (pintype "passive"))
      (node (ref "USBC1") (pin "A1") (pinfunction "GND_A1") (pintype "passive"))
      (node (ref "USBC1") (pin "A12") (pinfunction "GND_A12") (pintype "passive"))
      (node (ref "USBC1") (pin "B1") (pinfunction "GND_B1") (pintype "passive"))
      (node (ref "USBC1") (pin "B12") (pinfunction "GND_B12") (pintype "passive"))
      (node (ref "Y1") (pin "2") (pinfunction "GND_2") (pintype "power_in"))
      (node (ref "Y1") (pin "4") (pinfunction "GND_4") (pintype "power_in"))
    )
    (net (code "60") (name "Net-(LED1-A)") (class "Default")
      (node (ref "LED1") (pin "1") (pinfunction "A_1") (pintype "passive"))
      (node (ref "RN1") (pin "8") (pinfunction "8_8") (pintype "passive"))
    )
    (net (code "61") (name "Net-(LED2-A)") (class "Default")
      (node (ref "LED2") (pin "1") (pinfunction "A_1") (pintype "passive"))
      (node (ref "RN1") (pin "7") (pinfunction "7_7") (pintype "passive"))
    )
    (net (code "62") (name "Net-(LED3-A)") (class "Default")
      (node (ref "LED3") (pin "1") (pinfunction "A_1") (pintype "passive"))
      (node (ref "RN1") (pin "6") (pinfunction "6_6") (pintype "passive"))
    )
    (net (code "63") (name "Net-(LED4-A)") (class "Default")
      (node (ref "LED4") (pin "1") (pinfunction "A_1") (pintype "passive"))
      (node (ref "RN1") (pin "5") (pinfunction "5_5") (pintype "passive"))
    )
    (net (code "64") (name "Net-(LED5-A)") (class "Default")
      (node (ref "LED5") (pin "1") (pinfunction "A_1") (pintype "passive"))
      (node (ref "RN2") (pin "8") (pinfunction "8_8") (pintype "passive"))
    )
    (net (code "65") (name "Net-(LED6-A)") (class "Default")
      (node (ref "LED6") (pin "1") (pinfunction "A_1") (pintype "passive"))
      (node (ref "RN2") (pin "7") (pinfunction "7_7") (pintype "passive"))
    )
    (net (code "66") (name "Net-(LED7-A)") (class "Default")
      (node (ref "LED7") (pin "1") (pinfunction "A_1") (pintype "passive"))
      (node (ref "RN2") (pin "6") (pinfunction "6_6") (pintype "passive"))
    )
    (net (code "67") (name "Net-(OLED1-C1N)") (class "Default")
      (node (ref "C12") (pin "2") (pinfunction "2_2") (pintype "passive"))
      (node (ref "OLED1") (pin "5") (pinfunction "C1N_5") (pintype "passive"))
    )
    (net (code "68") (name "Net-(OLED1-C1P)") (class "Default")
      (node (ref "C12") (pin "1") (pinfunction "1_1") (pintype "passive"))
      (node (ref "OLED1") (pin "4") (pinfunction "C1P_4") (pintype "passive"))
    )
    (net (code "69") (name "Net-(OLED1-C2N)") (class "Default")
      (node (ref "C6") (pin "2") (pinfunction "2_2") (pintype "passive"))
      (node (ref "OLED1") (pin "3") (pinfunction "C2N_3") (pintype "passive"))
    )
    (net (code "70") (name "Net-(OLED1-C2P)") (class "Default")
      (node (ref "C6") (pin "1") (pinfunction "1_1") (pintype "passive"))
      (node (ref "OLED1") (pin "2") (pinfunction "C2P_2") (pintype "passive"))
    )
    (net (code "71") (name "Net-(OLED1-VCC)") (class "Default")
      (node (ref "C13") (pin "1") (pinfunction "1_1") (pintype "passive"))
      (node (ref "OLED1") (pin "28") (pinfunction "VCC_28") (pintype "passive"))
    )
    (net (code "72") (name "Net-(OLED1-VCOMH)") (class "Default")
      (node (ref "OLED1") (pin "27") (pinfunction "VCOMH_27") (pintype "passive"))
      (node (ref "R7") (pin "2") (pinfunction "2_2") (pintype "passive"))
    )
    (net (code "73") (name "Net-(Q1-S)") (class "Default")
      (node (ref "Q1") (pin "2") (pinfunction "S_2") (pintype "passive"))
      (node (ref "R6") (pin "2") (pinfunction "2_2") (pintype "passive"))
    )
    (net (code "74") (name "Net-(U2-RST)") (class "Default")
      (node (ref "C5") (pin "2") (pinfunction "2_2") (pintype "passive"))
      (node (ref "R1") (pin "2") (pinfunction "2_2") (pintype "passive"))
      (node (ref "U2") (pin "1") (pinfunction "RST_1") (pintype "input"))
    )
    (net (code "75") (name "Net-(U2-XI)") (class "Default")
      (node (ref "C9") (pin "2") (pinfunction "2_2") (pintype "passive"))
      (node (ref "U2") (pin "19") (pinfunction "XI_19") (pintype "bidirectional"))
      (node (ref "Y1") (pin "1") (pinfunction "1_1") (pintype "passive"))
    )
    (net (code "76") (name "Net-(U2-XO)") (class "Default")
      (node (ref "C8") (pin "2") (pinfunction "2_2") (pintype "passive"))
      (node (ref "U2") (pin "20") (pinfunction "XO_20") (pintype "bidirectional"))
      (node (ref "Y1") (pin "3") (pinfunction "3_3") (pintype "passive"))
    )
    (net (code "77") (name "Net-(U3-WP#(IO2))") (class "Default")
      (node (ref "R10") (pin "1") (pinfunction "1_1") (pintype "passive"))
      (node (ref "U3") (pin "3") (pinfunction "WP#(IO2)_3") (pintype "passive"))
    )
    (net (code "78") (name "Net-(U4-PF2-NRST)") (class "Default")
      (node (ref "C14") (pin "1") (pinfunction "1_1") (pintype "passive"))
      (node (ref "R8") (pin "1") (pinfunction "1_1") (pintype "passive"))
      (node (ref "U4") (pin "10") (pinfunction "PF2-NRST_10") (pintype "passive"))
    )
    (net (code "79") (name "Net-(U8-A)") (class "Default")
      (node (ref "R16") (pin "2") (pinfunction "2_2") (pintype "passive"))
      (node (ref "R17") (pin "2") (pinfunction "2_2") (pintype "passive"))
      (node (ref "U8") (pin "6") (pinfunction "A_6") (pintype "passive"))
    )
    (net (code "80") (name "Net-(U8-B)") (class "Default")
      (node (ref "R13") (pin "1") (pinfunction "1_1") (pintype "passive"))
      (node (ref "R14") (pin "2") (pinfunction "2_2") (pintype "passive"))
      (node (ref "U8") (pin "7") (pinfunction "B_7") (pintype "passive"))
    )
    (net (code "81") (name "unconnected-(JP4-Pad13)") (class "Default")
      (node (ref "JP4") (pin "13") (pinfunction "13_13") (pintype "passive"))
    )
    (net (code "82") (name "unconnected-(OLED1-D2-Pad20)") (class "Default")
      (node (ref "OLED1") (pin "20") (pinfunction "D2_20") (pintype "passive+no_connect"))
    )
    (net (code "83") (name "unconnected-(OLED1-VSS-Pad7)") (class "Default")
      (node (ref "OLED1") (pin "7") (pinfunction "VSS_7") (pintype "passive+no_connect"))
    )
    (net (code "84") (name "unconnected-(RN2-Pad5)") (class "Default")
      (node (ref "RN2") (pin "5") (pinfunction "5_5") (pintype "passive+no_connect"))
    )
    (net (code "85") (name "unconnected-(U2-RI0{slash}GPIO3-Pad11)") (class "Default")
      (node (ref "U2") (pin "11") (pinfunction "RI0/GPIO3_11") (pintype "bidirectional+no_connect"))
    )
    (net (code "86") (name "unconnected-(U2-RXD0{slash}SDA-Pad12)") (class "Default")
      (node (ref "U2") (pin "12") (pinfunction "RXD0/SDA_12") (pintype "bidirectional+no_connect"))
    )
    (net (code "87") (name "unconnected-(U4-PA4-Pad15)") (class "Default")
      (node (ref "U4") (pin "15") (pinfunction "PA4_15") (pintype "passive+no_connect"))
    )
    (net (code "88") (name "unconnected-(U4-PA8-Pad28)") (class "Default")
      (node (ref "U4") (pin "28") (pinfunction "PA8_28") (pintype "passive"))
    )
    (net (code "89") (name "unconnected-(U4-PA11[PA9]-Pad33)") (class "Default")
      (node (ref "U4") (pin "33") (pinfunction "PA11[PA9]_33") (pintype "passive"))
    )
    (net (code "90") (name "unconnected-(U4-PA12[PA10]-Pad34)") (class "Default")
      (node (ref "U4") (pin "34") (pinfunction "PA12[PA10]_34") (pintype "passive"))
    )
    (net (code "91") (name "unconnected-(U4-PB1-Pad20)") (class "Default")
      (node (ref "U4") (pin "20") (pinfunction "PB1_20") (pintype "passive"))
    )
    (net (code "92") (name "unconnected-(U4-PD3-Pad41)") (class "Default")
      (node (ref "U4") (pin "41") (pinfunction "PD3_41") (pintype "passive"))
    )
    (net (code "93") (name "unconnected-(U4-PF0-OSC_IN-Pad8)") (class "Default")
      (node (ref "U4") (pin "8") (pinfunction "PF0-OSC_IN_8") (pintype "passive"))
    )
    (net (code "94") (name "unconnected-(U4-PF1-OSC_OUT-Pad9)") (class "Default")
      (node (ref "U4") (pin "9") (pinfunction "PF1-OSC_OUT_9") (pintype "passive"))
    )
    (net (code "95") (name "unconnected-(USBC1-CC1-PadA5)") (class "Default")
      (node (ref "USBC1") (pin "A5") (pinfunction "CC1_A5") (pintype "passive+no_connect"))
    )
    (net (code "96") (name "unconnected-(USBC1-CC2-PadB5)") (class "Default")
      (node (ref "USBC1") (pin "B5") (pinfunction "CC2_B5") (pintype "passive+no_connect"))
    )
    (net (code "97") (name "unconnected-(USBC1-SBU1-PadA8)") (class "Default")
      (node (ref "USBC1") (pin "A8") (pinfunction "SBU1_A8") (pintype "passive+no_connect"))
    )
    (net (code "98") (name "unconnected-(USBC1-SBU2-PadB8)") (class "Default")
      (node (ref "USBC1") (pin "B8") (pinfunction "SBU2_B8") (pintype "passive+no_connect"))
    )
  )
)
